# untitled.net
KiCad netlist of a schematic drawn in EAGLE
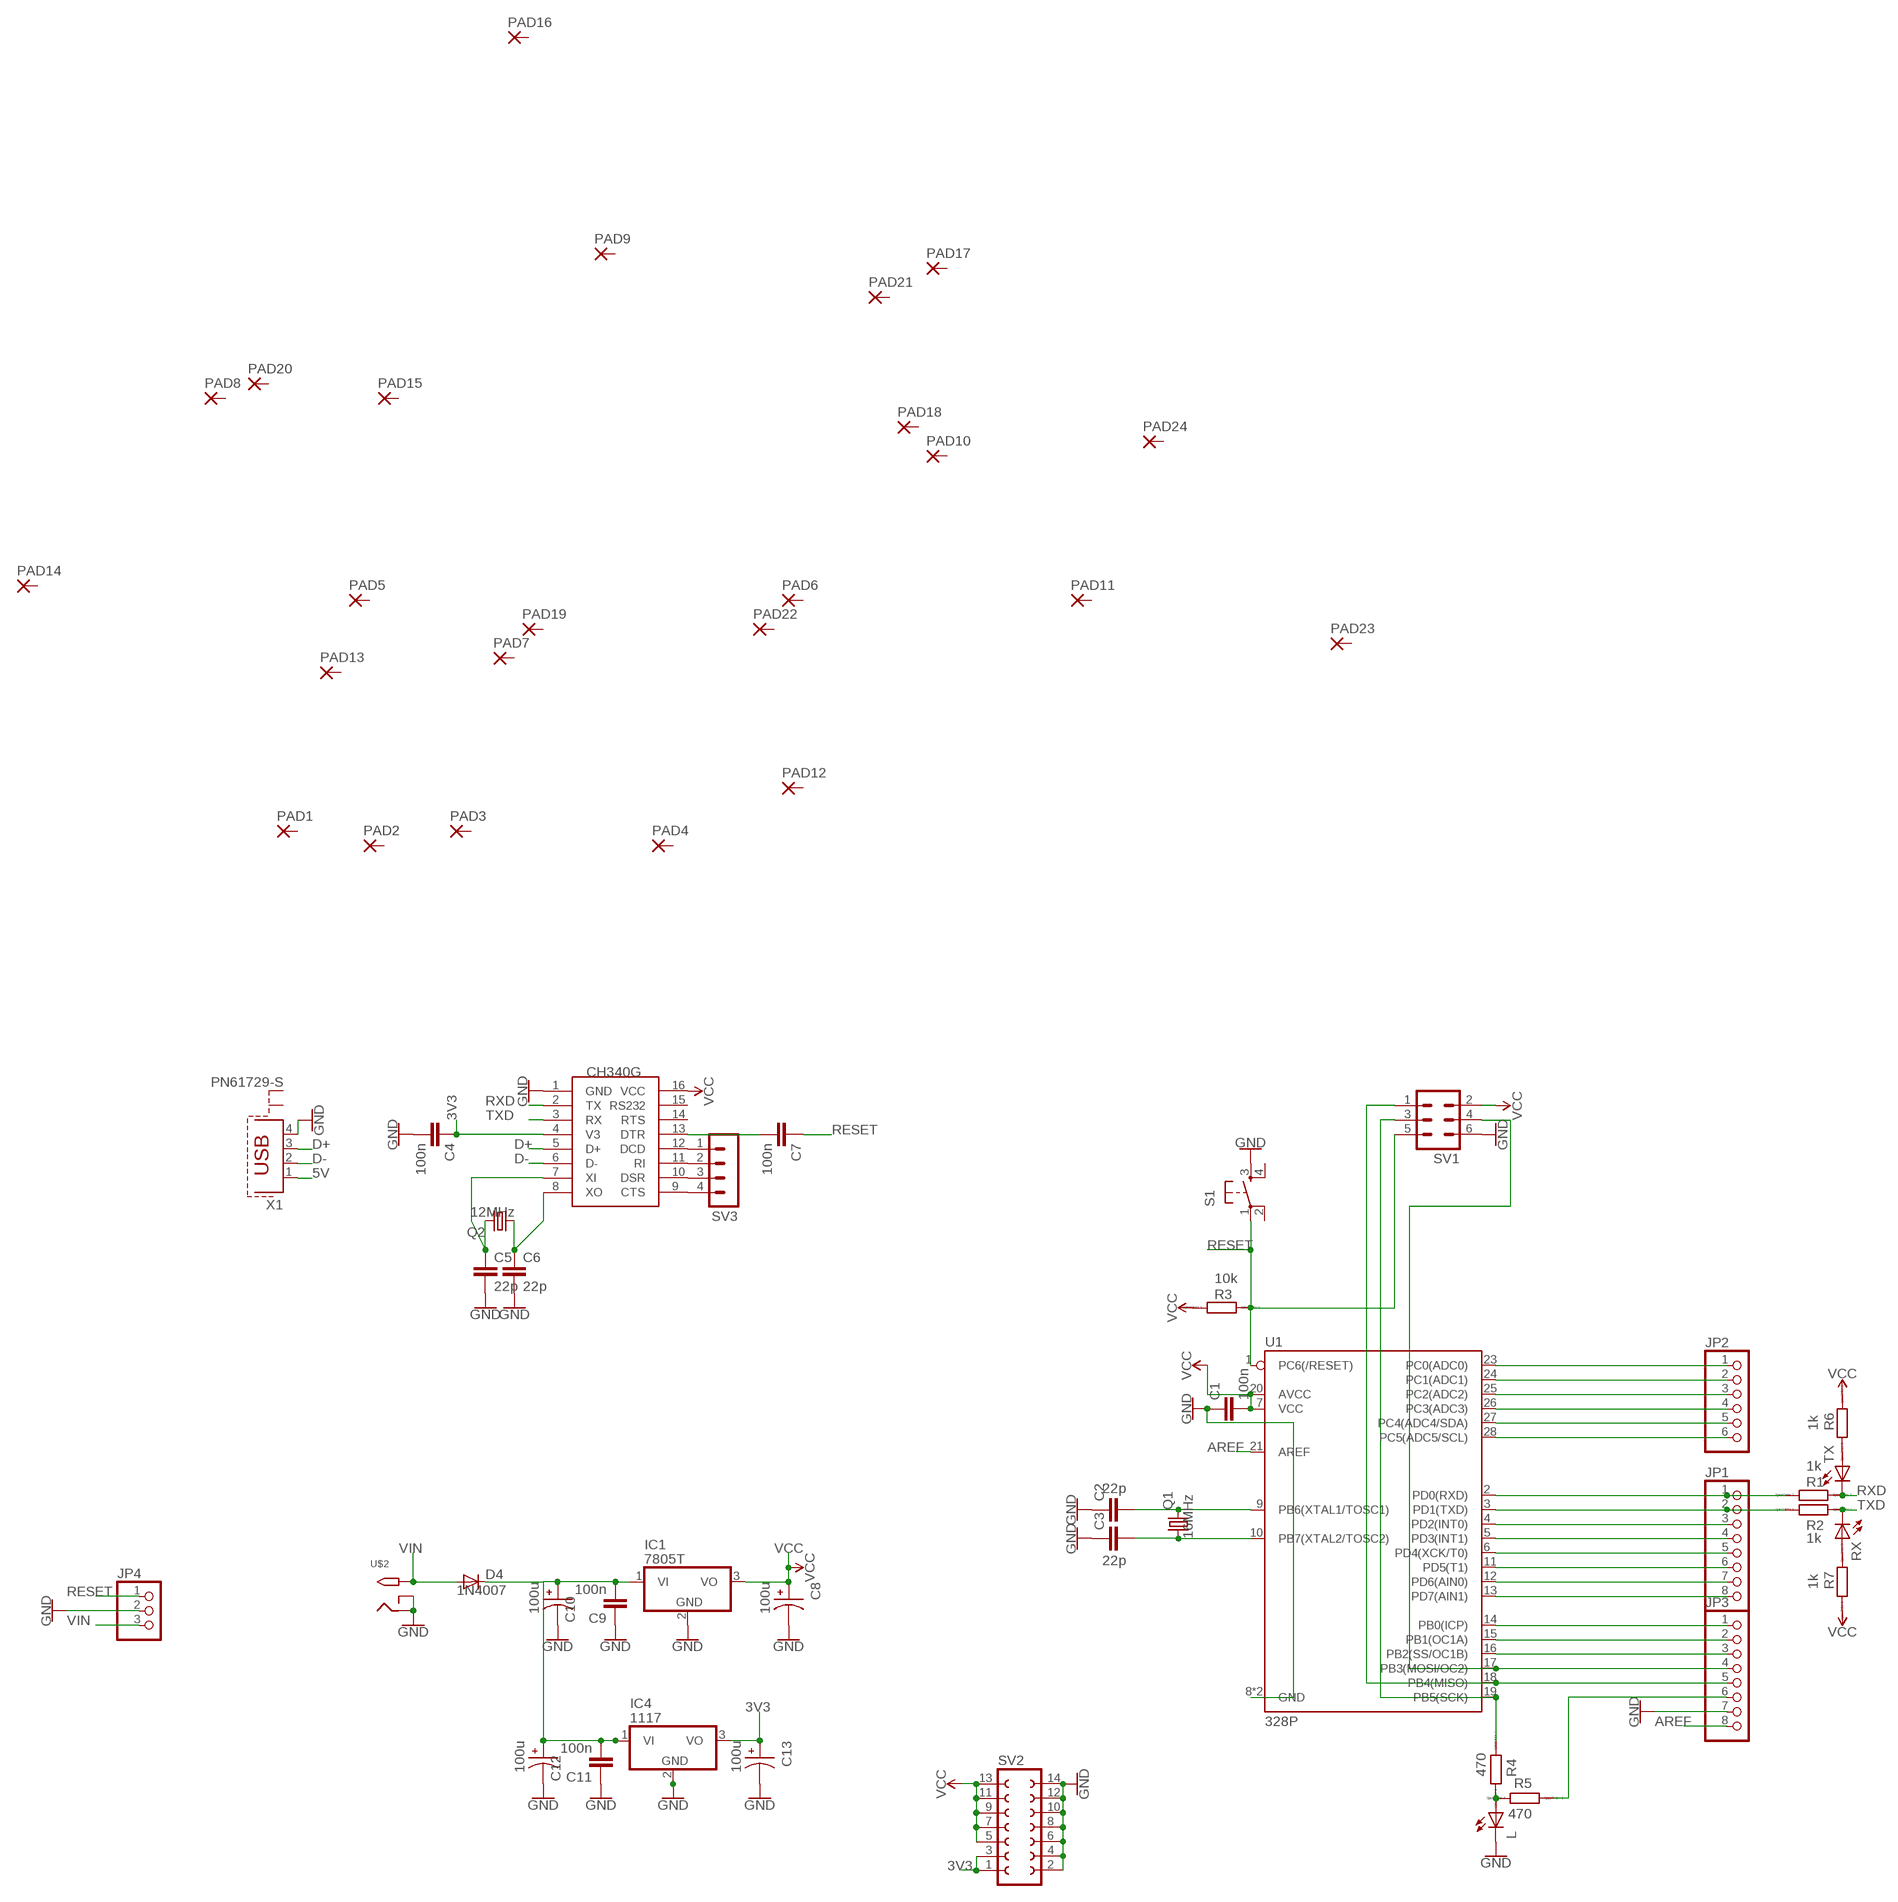
[diagram p0: schematic, sheet 1]

(export (version "E")
  (design (tool "Eeschema 10.0.6"))
  (components
    (comp (ref "C1")
      (value "100n")
      (footprint "eagle-import:C2.5-3")
      (libsource (lib "eagle-import") (part "C2,5-3"))
    )
    (comp (ref "C2")
      (value "22p")
      (footprint "eagle-import:C2.5-3")
      (libsource (lib "eagle-import") (part "C2,5-3"))
    )
    (comp (ref "C3")
      (value "22p")
      (footprint "eagle-import:C2.5-3")
      (libsource (lib "eagle-import") (part "C2,5-3"))
    )
    (comp (ref "C4")
      (value "100n")
      (footprint "eagle-import:C2.5-3")
      (libsource (lib "eagle-import") (part "C2,5-3"))
    )
    (comp (ref "C5")
      (value "22p")
      (footprint "eagle-import:C2.5-3")
      (libsource (lib "eagle-import") (part "C2,5-3"))
    )
    (comp (ref "C6")
      (value "22p")
      (footprint "eagle-import:C2.5-3")
      (libsource (lib "eagle-import") (part "C2,5-3"))
    )
    (comp (ref "C7")
      (value "100n")
      (footprint "eagle-import:C2.5-3")
      (libsource (lib "eagle-import") (part "C2,5-3"))
    )
    (comp (ref "C8")
      (value "100u")
      (footprint "eagle-import:CAPPRD500W50D500H1100")
      (fields (field (name "MF") "Panasonic") (field (name "MP") "ECA1VHG100B"))
      (libsource (lib "eagle-import") (part "ECA1VHG100B"))
    )
    (comp (ref "C9")
      (value "100n")
      (footprint "eagle-import:C2.5-3")
      (libsource (lib "eagle-import") (part "C2,5-3"))
    )
    (comp (ref "C10")
      (value "100u")
      (footprint "eagle-import:CAPPRD500W50D500H1100")
      (fields (field (name "MF") "Panasonic") (field (name "MP") "ECA1VHG100B"))
      (libsource (lib "eagle-import") (part "ECA1VHG100B"))
    )
    (comp (ref "C11")
      (value "100n")
      (footprint "eagle-import:C2.5-3")
      (libsource (lib "eagle-import") (part "C2,5-3"))
    )
    (comp (ref "C12")
      (value "100u")
      (footprint "eagle-import:CAPPRD500W50D500H1100")
      (fields (field (name "MF") "Panasonic") (field (name "MP") "ECA1VHG100B"))
      (libsource (lib "eagle-import") (part "ECA1VHG100B"))
    )
    (comp (ref "C13")
      (value "100u")
      (footprint "eagle-import:CAPPRD500W50D500H1100")
      (fields (field (name "MF") "Panasonic") (field (name "MP") "ECA1VHG100B"))
      (libsource (lib "eagle-import") (part "ECA1VHG100B"))
    )
    (comp (ref "D4")
      (value "1N4007")
      (footprint "eagle-import:DO41-10")
      (libsource (lib "eagle-import") (part "1N4004"))
    )
    (comp (ref "IC1")
      (value "7805T")
      (footprint "eagle-import:TO220H")
      (libsource (lib "eagle-import") (part "78T05"))
    )
    (comp (ref "IC4")
      (value "1117")
      (footprint "eagle-import:TO220H")
      (libsource (lib "eagle-import") (part "78T05"))
    )
    (comp (ref "JP1")
      (value "PINHD-1X8CLEANBIG")
      (footprint "eagle-import:1X08-CLEANBIG")
      (libsource (lib "eagle-import") (part "PINHD-1X8CLEANBIG"))
    )
    (comp (ref "JP2")
      (value "PINHD-1X6")
      (footprint "eagle-import:1X06")
      (libsource (lib "eagle-import") (part "PINHD-1X6"))
    )
    (comp (ref "JP3")
      (value "PINHD-1X8CLEANBIG")
      (footprint "eagle-import:1X08-CLEANBIG")
      (libsource (lib "eagle-import") (part "PINHD-1X8CLEANBIG"))
    )
    (comp (ref "JP4")
      (value "PINHD-1X3")
      (footprint "eagle-import:1X03")
      (libsource (lib "eagle-import") (part "PINHD-1X3"))
    )
    (comp (ref "L")
      (value "LED3MM")
      (footprint "eagle-import:LED3MM")
      (libsource (lib "eagle-import") (part "LED3MM"))
    )
    (comp (ref "PAD1")
      (value "SMD5")
      (footprint "eagle-import:SMD2,54-5,08")
      (libsource (lib "eagle-import") (part "SMD5"))
    )
    (comp (ref "PAD2")
      (value "SMD5")
      (footprint "eagle-import:SMD2,54-5,08")
      (libsource (lib "eagle-import") (part "SMD5"))
    )
    (comp (ref "PAD3")
      (value "SMD5")
      (footprint "eagle-import:SMD2,54-5,08")
      (libsource (lib "eagle-import") (part "SMD5"))
    )
    (comp (ref "PAD4")
      (value "SMD5")
      (footprint "eagle-import:SMD2,54-5,08")
      (libsource (lib "eagle-import") (part "SMD5"))
    )
    (comp (ref "PAD5")
      (value "SMD5")
      (footprint "eagle-import:SMD2,54-5,08")
      (libsource (lib "eagle-import") (part "SMD5"))
    )
    (comp (ref "PAD6")
      (value "SMD5")
      (footprint "eagle-import:SMD2,54-5,08")
      (libsource (lib "eagle-import") (part "SMD5"))
    )
    (comp (ref "PAD7")
      (value "SMD5")
      (footprint "eagle-import:SMD2,54-5,08")
      (libsource (lib "eagle-import") (part "SMD5"))
    )
    (comp (ref "PAD8")
      (value "SMD5")
      (footprint "eagle-import:SMD2,54-5,08")
      (libsource (lib "eagle-import") (part "SMD5"))
    )
    (comp (ref "PAD9")
      (value "SMD5")
      (footprint "eagle-import:SMD2,54-5,08")
      (libsource (lib "eagle-import") (part "SMD5"))
    )
    (comp (ref "PAD10")
      (value "SMD5")
      (footprint "eagle-import:SMD2,54-5,08")
      (libsource (lib "eagle-import") (part "SMD5"))
    )
    (comp (ref "PAD11")
      (value "SMD5")
      (footprint "eagle-import:SMD2,54-5,08")
      (libsource (lib "eagle-import") (part "SMD5"))
    )
    (comp (ref "PAD12")
      (value "SMD5")
      (footprint "eagle-import:SMD2,54-5,08")
      (libsource (lib "eagle-import") (part "SMD5"))
    )
    (comp (ref "PAD13")
      (value "SMD5")
      (footprint "eagle-import:SMD2,54-5,08")
      (libsource (lib "eagle-import") (part "SMD5"))
    )
    (comp (ref "PAD14")
      (value "SMD5")
      (footprint "eagle-import:SMD2,54-5,08")
      (libsource (lib "eagle-import") (part "SMD5"))
    )
    (comp (ref "PAD15")
      (value "SMD5")
      (footprint "eagle-import:SMD2,54-5,08")
      (libsource (lib "eagle-import") (part "SMD5"))
    )
    (comp (ref "PAD16")
      (value "SMD5")
      (footprint "eagle-import:SMD2,54-5,08")
      (libsource (lib "eagle-import") (part "SMD5"))
    )
    (comp (ref "PAD17")
      (value "SMD5")
      (footprint "eagle-import:SMD2,54-5,08")
      (libsource (lib "eagle-import") (part "SMD5"))
    )
    (comp (ref "PAD18")
      (value "SMD5")
      (footprint "eagle-import:SMD2,54-5,08")
      (libsource (lib "eagle-import") (part "SMD5"))
    )
    (comp (ref "PAD19")
      (value "SMD5")
      (footprint "eagle-import:SMD2,54-5,08")
      (libsource (lib "eagle-import") (part "SMD5"))
    )
    (comp (ref "PAD20")
      (value "SMD5")
      (footprint "eagle-import:SMD2,54-5,08")
      (libsource (lib "eagle-import") (part "SMD5"))
    )
    (comp (ref "PAD21")
      (value "SMD5")
      (footprint "eagle-import:SMD2,54-5,08")
      (libsource (lib "eagle-import") (part "SMD5"))
    )
    (comp (ref "PAD22")
      (value "SMD5")
      (footprint "eagle-import:SMD2,54-5,08")
      (libsource (lib "eagle-import") (part "SMD5"))
    )
    (comp (ref "PAD23")
      (value "SMD5")
      (footprint "eagle-import:SMD2,54-5,08")
      (libsource (lib "eagle-import") (part "SMD5"))
    )
    (comp (ref "PAD24")
      (value "SMD5")
      (footprint "eagle-import:SMD2,54-5,08")
      (libsource (lib "eagle-import") (part "SMD5"))
    )
    (comp (ref "Q1")
      (value "16MHz")
      (footprint "eagle-import:HC49_S")
      (libsource (lib "eagle-import") (part "CRYSTALHC49S"))
    )
    (comp (ref "Q2")
      (value "12MHz")
      (footprint "eagle-import:HC49_S")
      (libsource (lib "eagle-import") (part "CRYSTALHC49S"))
    )
    (comp (ref "R1")
      (value "1k")
      (footprint "eagle-import:0204_7")
      (libsource (lib "eagle-import") (part "R0204/7"))
    )
    (comp (ref "R2")
      (value "1k")
      (footprint "eagle-import:0204_7")
      (libsource (lib "eagle-import") (part "R0204/7"))
    )
    (comp (ref "R3")
      (value "10k")
      (footprint "eagle-import:0204_7")
      (libsource (lib "eagle-import") (part "R0204/7"))
    )
    (comp (ref "R4")
      (value "470")
      (footprint "eagle-import:0204_7")
      (libsource (lib "eagle-import") (part "R0204/7"))
    )
    (comp (ref "R5")
      (value "470")
      (footprint "eagle-import:0204_7")
      (libsource (lib "eagle-import") (part "R0204/7"))
    )
    (comp (ref "R6")
      (value "1k")
      (footprint "eagle-import:0204_7")
      (libsource (lib "eagle-import") (part "R0204/7"))
    )
    (comp (ref "R7")
      (value "1k")
      (footprint "eagle-import:0204_7")
      (libsource (lib "eagle-import") (part "R0204/7"))
    )
    (comp (ref "RX")
      (value "LED3MM")
      (footprint "eagle-import:LED3MM")
      (libsource (lib "eagle-import") (part "LED3MM"))
    )
    (comp (ref "S1")
      (value "TAC_SWITCHPTH")
      (footprint "eagle-import:TACTILE-PTH")
      (libsource (lib "eagle-import") (part "TAC_SWITCHPTH"))
    )
    (comp (ref "SV1")
      (value "MA03-2")
      (footprint "eagle-import:MA03-2")
      (libsource (lib "eagle-import") (part "MA03-2"))
    )
    (comp (ref "SV2")
      (value "FE07-2")
      (footprint "eagle-import:FE07-2")
      (libsource (lib "eagle-import") (part "FE07-2"))
    )
    (comp (ref "SV3")
      (value "MA04-1")
      (footprint "eagle-import:MA04-1")
      (libsource (lib "eagle-import") (part "MA04-1"))
    )
    (comp (ref "TX")
      (value "LED3MM")
      (footprint "eagle-import:LED3MM")
      (libsource (lib "eagle-import") (part "LED3MM"))
    )
    (comp (ref "U$1")
      (value "CH340G")
      (footprint "eagle-import:SOIC16")
      (libsource (lib "eagle-import") (part "CH340G"))
    )
    (comp (ref "U$2")
      (value "2.1MMJACKTHM")
      (footprint "eagle-import:PJ-102A")
      (libsource (lib "eagle-import") (part "2.1MMJACKTHM"))
    )
    (comp (ref "U1")
      (value "328P")
      (footprint "eagle-import:DIP28")
      (libsource (lib "eagle-import") (part "ATMEGA328P_PDIP"))
    )
    (comp (ref "X1")
      (value "PN61729-S")
      (footprint "eagle-import:PN61729-S")
      (libsource (lib "eagle-import") (part "PN61729-S"))
    )
  )
  (nets
    (net (code "1") (name "/3V3") (class "Default")
      (node (ref "C13") (pin "P") (pinfunction "P_P") (pintype "passive"))
      (node (ref "C4") (pin "1") (pinfunction "1_1") (pintype "passive"))
      (node (ref "IC4") (pin "3") (pinfunction "VO_3") (pintype "passive"))
      (node (ref "SV2") (pin "1") (pinfunction "1_1") (pintype "passive"))
      (node (ref "SV2") (pin "3") (pinfunction "3_3") (pintype "passive"))
      (node (ref "U$1") (pin "4") (pinfunction "V3_4") (pintype "bidirectional"))
    )
    (net (code "2") (name "/5V") (class "Default")
      (node (ref "X1") (pin "1") (pinfunction "1_1") (pintype "passive"))
    )
    (net (code "3") (name "/AREF") (class "Default")
      (node (ref "JP3") (pin "8") (pinfunction "8_8") (pintype "passive"))
      (node (ref "U1") (pin "21") (pinfunction "AREF_21") (pintype "bidirectional"))
    )
    (net (code "4") (name "/D+") (class "Default")
      (node (ref "U$1") (pin "5") (pinfunction "D+_5") (pintype "bidirectional"))
      (node (ref "X1") (pin "3") (pinfunction "3_3") (pintype "passive"))
    )
    (net (code "5") (name "/D-") (class "Default")
      (node (ref "U$1") (pin "6") (pinfunction "D-_6") (pintype "bidirectional"))
      (node (ref "X1") (pin "2") (pinfunction "2_2") (pintype "passive"))
    )
    (net (code "6") (name "/RESET") (class "Default")
      (node (ref "C7") (pin "1") (pinfunction "1_1") (pintype "passive"))
      (node (ref "JP4") (pin "1") (pinfunction "1_1") (pintype "passive"))
      (node (ref "R3") (pin "2") (pinfunction "2_2") (pintype "passive"))
      (node (ref "S1") (pin "1") (pinfunction "1_1") (pintype "passive"))
      (node (ref "SV1") (pin "5") (pinfunction "5_5") (pintype "passive"))
      (node (ref "U1") (pin "1") (pinfunction "PC6(/RESET)_1") (pintype "bidirectional"))
    )
    (net (code "7") (name "/RXD") (class "Default")
      (node (ref "R1") (pin "2") (pinfunction "2_2") (pintype "passive"))
      (node (ref "TX") (pin "K") (pinfunction "C_K") (pintype "passive"))
      (node (ref "U$1") (pin "2") (pinfunction "TX_2") (pintype "bidirectional"))
    )
    (net (code "8") (name "/TXD") (class "Default")
      (node (ref "R2") (pin "2") (pinfunction "2_2") (pintype "passive"))
      (node (ref "RX") (pin "K") (pinfunction "C_K") (pintype "passive"))
      (node (ref "U$1") (pin "3") (pinfunction "RX_3") (pintype "bidirectional"))
    )
    (net (code "9") (name "/VIN") (class "Default")
      (node (ref "D4") (pin "A") (pinfunction "A_A") (pintype "passive"))
      (node (ref "JP4") (pin "3") (pinfunction "3_3") (pintype "passive"))
      (node (ref "U$2") (pin "TIP") (pinfunction "TIP_TIP") (pintype "bidirectional"))
    )
    (net (code "10") (name "GND") (class "Default")
      (node (ref "C1") (pin "1") (pinfunction "1_1") (pintype "passive"))
      (node (ref "C10") (pin "N") (pinfunction "N_N") (pintype "passive"))
      (node (ref "C11") (pin "1") (pinfunction "1_1") (pintype "passive"))
      (node (ref "C12") (pin "N") (pinfunction "N_N") (pintype "passive"))
      (node (ref "C13") (pin "N") (pinfunction "N_N") (pintype "passive"))
      (node (ref "C2") (pin "1") (pinfunction "1_1") (pintype "passive"))
      (node (ref "C3") (pin "1") (pinfunction "1_1") (pintype "passive"))
      (node (ref "C4") (pin "2") (pinfunction "2_2") (pintype "passive"))
      (node (ref "C5") (pin "2") (pinfunction "2_2") (pintype "passive"))
      (node (ref "C6") (pin "2") (pinfunction "2_2") (pintype "passive"))
      (node (ref "C8") (pin "N") (pinfunction "N_N") (pintype "passive"))
      (node (ref "C9") (pin "1") (pinfunction "1_1") (pintype "passive"))
      (node (ref "IC1") (pin "2") (pinfunction "GND_2") (pintype "passive"))
      (node (ref "IC4") (pin "2") (pinfunction "GND_2") (pintype "passive"))
      (node (ref "JP3") (pin "7") (pinfunction "7_7") (pintype "passive"))
      (node (ref "JP4") (pin "2") (pinfunction "2_2") (pintype "passive"))
      (node (ref "L") (pin "K") (pinfunction "C_K") (pintype "passive"))
      (node (ref "S1") (pin "3") (pinfunction "3_3") (pintype "passive"))
      (node (ref "SV1") (pin "6") (pinfunction "6_6") (pintype "passive"))
      (node (ref "SV2") (pin "10") (pinfunction "10_10") (pintype "passive"))
      (node (ref "SV2") (pin "12") (pinfunction "12_12") (pintype "passive"))
      (node (ref "SV2") (pin "14") (pinfunction "14_14") (pintype "passive"))
      (node (ref "SV2") (pin "2") (pinfunction "2_2") (pintype "passive"))
      (node (ref "SV2") (pin "4") (pinfunction "4_4") (pintype "passive"))
      (node (ref "SV2") (pin "6") (pinfunction "6_6") (pintype "passive"))
      (node (ref "SV2") (pin "8") (pinfunction "8_8") (pintype "passive"))
      (node (ref "U$1") (pin "1") (pinfunction "GND_1") (pintype "bidirectional"))
      (node (ref "U$2") (pin "RING") (pinfunction "RING_RING") (pintype "bidirectional"))
      (node (ref "U$2") (pin "RING_SW") (pinfunction "RING_SW_RING_SW") (pintype "bidirectional"))
      (node (ref "U1") (pin "22") (pinfunction "GND_22") (pintype "bidirectional"))
      (node (ref "U1") (pin "8") (pinfunction "GND_8") (pintype "bidirectional"))
      (node (ref "X1") (pin "4") (pinfunction "4_4") (pintype "passive"))
    )
    (net (code "11") (name "Net-(IC1-VI)") (class "Default")
      (node (ref "C10") (pin "P") (pinfunction "P_P") (pintype "passive"))
      (node (ref "C11") (pin "2") (pinfunction "2_2") (pintype "passive"))
      (node (ref "C12") (pin "P") (pinfunction "P_P") (pintype "passive"))
      (node (ref "C9") (pin "2") (pinfunction "2_2") (pintype "passive"))
      (node (ref "D4") (pin "C") (pinfunction "C_C") (pintype "passive"))
      (node (ref "IC1") (pin "1") (pinfunction "VI_1") (pintype "input"))
      (node (ref "IC4") (pin "1") (pinfunction "VI_1") (pintype "input"))
    )
    (net (code "12") (name "Net-(JP3-Pad6)") (class "Default")
      (node (ref "JP3") (pin "6") (pinfunction "6_6") (pintype "passive"))
      (node (ref "R5") (pin "1") (pinfunction "1_1") (pintype "passive"))
    )
    (net (code "13") (name "Net-(L-PadA)") (class "Default")
      (node (ref "L") (pin "A") (pinfunction "A_A") (pintype "passive"))
      (node (ref "R4") (pin "1") (pinfunction "1_1") (pintype "passive"))
      (node (ref "R5") (pin "2") (pinfunction "2_2") (pintype "passive"))
    )
    (net (code "14") (name "Net-(R6-Pad1)") (class "Default")
      (node (ref "R6") (pin "1") (pinfunction "1_1") (pintype "passive"))
      (node (ref "TX") (pin "A") (pinfunction "A_A") (pintype "passive"))
    )
    (net (code "15") (name "Net-(R7-Pad2)") (class "Default")
      (node (ref "R7") (pin "2") (pinfunction "2_2") (pintype "passive"))
      (node (ref "RX") (pin "A") (pinfunction "A_A") (pintype "passive"))
    )
    (net (code "16") (name "Net-(U$1-CTS)") (class "Default")
      (node (ref "SV3") (pin "4") (pinfunction "4_4") (pintype "passive"))
      (node (ref "U$1") (pin "9") (pinfunction "CTS_9") (pintype "bidirectional"))
    )
    (net (code "17") (name "Net-(U$1-DCD)") (class "Default")
      (node (ref "SV3") (pin "1") (pinfunction "1_1") (pintype "passive"))
      (node (ref "U$1") (pin "12") (pinfunction "DCD_12") (pintype "bidirectional"))
    )
    (net (code "18") (name "Net-(U$1-DSR)") (class "Default")
      (node (ref "SV3") (pin "3") (pinfunction "3_3") (pintype "passive"))
      (node (ref "U$1") (pin "10") (pinfunction "DSR_10") (pintype "bidirectional"))
    )
    (net (code "19") (name "Net-(U$1-DTR)") (class "Default")
      (node (ref "C7") (pin "2") (pinfunction "2_2") (pintype "passive"))
      (node (ref "U$1") (pin "13") (pinfunction "DTR_13") (pintype "bidirectional"))
    )
    (net (code "20") (name "Net-(U$1-RI)") (class "Default")
      (node (ref "SV3") (pin "2") (pinfunction "2_2") (pintype "passive"))
      (node (ref "U$1") (pin "11") (pinfunction "RI_11") (pintype "bidirectional"))
    )
    (net (code "21") (name "Net-(U$1-XI)") (class "Default")
      (node (ref "C5") (pin "1") (pinfunction "1_1") (pintype "passive"))
      (node (ref "Q2") (pin "2") (pinfunction "2_2") (pintype "passive"))
      (node (ref "U$1") (pin "7") (pinfunction "XI_7") (pintype "bidirectional"))
    )
    (net (code "22") (name "Net-(U$1-XO)") (class "Default")
      (node (ref "C6") (pin "1") (pinfunction "1_1") (pintype "passive"))
      (node (ref "Q2") (pin "1") (pinfunction "1_1") (pintype "passive"))
      (node (ref "U$1") (pin "8") (pinfunction "XO_8") (pintype "bidirectional"))
    )
    (net (code "23") (name "Net-(U1-PB0(ICP))") (class "Default")
      (node (ref "JP3") (pin "1") (pinfunction "1_1") (pintype "passive"))
      (node (ref "U1") (pin "14") (pinfunction "PB0(ICP)_14") (pintype "bidirectional"))
    )
    (net (code "24") (name "Net-(U1-PB1(OC1A))") (class "Default")
      (node (ref "JP3") (pin "2") (pinfunction "2_2") (pintype "passive"))
      (node (ref "U1") (pin "15") (pinfunction "PB1(OC1A)_15") (pintype "bidirectional"))
    )
    (net (code "25") (name "Net-(U1-PB2(SS{slash}OC1B))") (class "Default")
      (node (ref "JP3") (pin "3") (pinfunction "3_3") (pintype "passive"))
      (node (ref "U1") (pin "16") (pinfunction "PB2(SS/OC1B)_16") (pintype "bidirectional"))
    )
    (net (code "26") (name "Net-(U1-PB3(MOSI{slash}OC2))") (class "Default")
      (node (ref "JP3") (pin "4") (pinfunction "4_4") (pintype "passive"))
      (node (ref "SV1") (pin "4") (pinfunction "4_4") (pintype "passive"))
      (node (ref "U1") (pin "17") (pinfunction "PB3(MOSI/OC2)_17") (pintype "bidirectional"))
    )
    (net (code "27") (name "Net-(U1-PB4(MISO))") (class "Default")
      (node (ref "JP3") (pin "5") (pinfunction "5_5") (pintype "passive"))
      (node (ref "SV1") (pin "1") (pinfunction "1_1") (pintype "passive"))
      (node (ref "U1") (pin "18") (pinfunction "PB4(MISO)_18") (pintype "bidirectional"))
    )
    (net (code "28") (name "Net-(U1-PB5(SCK))") (class "Default")
      (node (ref "R4") (pin "2") (pinfunction "2_2") (pintype "passive"))
      (node (ref "SV1") (pin "3") (pinfunction "3_3") (pintype "passive"))
      (node (ref "U1") (pin "19") (pinfunction "PB5(SCK)_19") (pintype "bidirectional"))
    )
    (net (code "29") (name "Net-(U1-PB6(XTAL1{slash}TOSC1))") (class "Default")
      (node (ref "C2") (pin "2") (pinfunction "2_2") (pintype "passive"))
      (node (ref "Q1") (pin "2") (pinfunction "2_2") (pintype "passive"))
      (node (ref "U1") (pin "9") (pinfunction "PB6(XTAL1/TOSC1)_9") (pintype "bidirectional"))
    )
    (net (code "30") (name "Net-(U1-PB7(XTAL2{slash}TOSC2))") (class "Default")
      (node (ref "C3") (pin "2") (pinfunction "2_2") (pintype "passive"))
      (node (ref "Q1") (pin "1") (pinfunction "1_1") (pintype "passive"))
      (node (ref "U1") (pin "10") (pinfunction "PB7(XTAL2/TOSC2)_10") (pintype "bidirectional"))
    )
    (net (code "31") (name "Net-(U1-PC0(ADC0))") (class "Default")
      (node (ref "JP2") (pin "1") (pinfunction "1_1") (pintype "passive"))
      (node (ref "U1") (pin "23") (pinfunction "PC0(ADC0)_23") (pintype "bidirectional"))
    )
    (net (code "32") (name "Net-(U1-PC1(ADC1))") (class "Default")
      (node (ref "JP2") (pin "2") (pinfunction "2_2") (pintype "passive"))
      (node (ref "U1") (pin "24") (pinfunction "PC1(ADC1)_24") (pintype "bidirectional"))
    )
    (net (code "33") (name "Net-(U1-PC2(ADC2))") (class "Default")
      (node (ref "JP2") (pin "3") (pinfunction "3_3") (pintype "passive"))
      (node (ref "U1") (pin "25") (pinfunction "PC2(ADC2)_25") (pintype "bidirectional"))
    )
    (net (code "34") (name "Net-(U1-PC3(ADC3))") (class "Default")
      (node (ref "JP2") (pin "4") (pinfunction "4_4") (pintype "passive"))
      (node (ref "U1") (pin "26") (pinfunction "PC3(ADC3)_26") (pintype "bidirectional"))
    )
    (net (code "35") (name "Net-(U1-PC4(ADC4{slash}SDA))") (class "Default")
      (node (ref "JP2") (pin "5") (pinfunction "5_5") (pintype "passive"))
      (node (ref "U1") (pin "27") (pinfunction "PC4(ADC4/SDA)_27") (pintype "bidirectional"))
    )
    (net (code "36") (name "Net-(U1-PC5(ADC5{slash}SCL))") (class "Default")
      (node (ref "JP2") (pin "6") (pinfunction "6_6") (pintype "passive"))
      (node (ref "U1") (pin "28") (pinfunction "PC5(ADC5/SCL)_28") (pintype "bidirectional"))
    )
    (net (code "37") (name "Net-(U1-PD0(RXD))") (class "Default")
      (node (ref "JP1") (pin "1") (pinfunction "1_1") (pintype "passive"))
      (node (ref "R1") (pin "1") (pinfunction "1_1") (pintype "passive"))
      (node (ref "U1") (pin "2") (pinfunction "PD0(RXD)_2") (pintype "bidirectional"))
    )
    (net (code "38") (name "Net-(U1-PD1(TXD))") (class "Default")
      (node (ref "JP1") (pin "2") (pinfunction "2_2") (pintype "passive"))
      (node (ref "R2") (pin "1") (pinfunction "1_1") (pintype "passive"))
      (node (ref "U1") (pin "3") (pinfunction "PD1(TXD)_3") (pintype "bidirectional"))
    )
    (net (code "39") (name "Net-(U1-PD2(INT0))") (class "Default")
      (node (ref "JP1") (pin "3") (pinfunction "3_3") (pintype "passive"))
      (node (ref "U1") (pin "4") (pinfunction "PD2(INT0)_4") (pintype "bidirectional"))
    )
    (net (code "40") (name "Net-(U1-PD3(INT1))") (class "Default")
      (node (ref "JP1") (pin "4") (pinfunction "4_4") (pintype "passive"))
      (node (ref "U1") (pin "5") (pinfunction "PD3(INT1)_5") (pintype "bidirectional"))
    )
    (net (code "41") (name "Net-(U1-PD4(XCK{slash}T0))") (class "Default")
      (node (ref "JP1") (pin "5") (pinfunction "5_5") (pintype "passive"))
      (node (ref "U1") (pin "6") (pinfunction "PD4(XCK/T0)_6") (pintype "bidirectional"))
    )
    (net (code "42") (name "Net-(U1-PD5(T1))") (class "Default")
      (node (ref "JP1") (pin "6") (pinfunction "6_6") (pintype "passive"))
      (node (ref "U1") (pin "11") (pinfunction "PD5(T1)_11") (pintype "bidirectional"))
    )
    (net (code "43") (name "Net-(U1-PD6(AIN0))") (class "Default")
      (node (ref "JP1") (pin "7") (pinfunction "7_7") (pintype "passive"))
      (node (ref "U1") (pin "12") (pinfunction "PD6(AIN0)_12") (pintype "bidirectional"))
    )
    (net (code "44") (name "Net-(U1-PD7(AIN1))") (class "Default")
      (node (ref "JP1") (pin "8") (pinfunction "8_8") (pintype "passive"))
      (node (ref "U1") (pin "13") (pinfunction "PD7(AIN1)_13") (pintype "bidirectional"))
    )
    (net (code "45") (name "VCC") (class "Default")
      (node (ref "C1") (pin "2") (pinfunction "2_2") (pintype "passive"))
      (node (ref "C8") (pin "P") (pinfunction "P_P") (pintype "passive"))
      (node (ref "IC1") (pin "3") (pinfunction "VO_3") (pintype "passive"))
      (node (ref "R3") (pin "1") (pinfunction "1_1") (pintype "passive"))
      (node (ref "R6") (pin "2") (pinfunction "2_2") (pintype "passive"))
      (node (ref "R7") (pin "1") (pinfunction "1_1") (pintype "passive"))
      (node (ref "SV1") (pin "2") (pinfunction "2_2") (pintype "passive"))
      (node (ref "SV2") (pin "11") (pinfunction "11_11") (pintype "passive"))
      (node (ref "SV2") (pin "13") (pinfunction "13_13") (pintype "passive"))
      (node (ref "SV2") (pin "5") (pinfunction "5_5") (pintype "passive"))
      (node (ref "SV2") (pin "7") (pinfunction "7_7") (pintype "passive"))
      (node (ref "SV2") (pin "9") (pinfunction "9_9") (pintype "passive"))
      (node (ref "U$1") (pin "16") (pinfunction "VCC_16") (pintype "bidirectional"))
      (node (ref "U1") (pin "20") (pinfunction "AVCC_20") (pintype "bidirectional"))
      (node (ref "U1") (pin "7") (pinfunction "VCC_7") (pintype "bidirectional"))
    )
    (net (code "46") (name "unconnected-(PAD1-P-Pad1)") (class "Default")
      (node (ref "PAD1") (pin "1") (pinfunction "P_1") (pintype "passive"))
    )
    (net (code "47") (name "unconnected-(PAD2-P-Pad1)") (class "Default")
      (node (ref "PAD2") (pin "1") (pinfunction "P_1") (pintype "passive"))
    )
    (net (code "48") (name "unconnected-(PAD3-P-Pad1)") (class "Default")
      (node (ref "PAD3") (pin "1") (pinfunction "P_1") (pintype "passive"))
    )
    (net (code "49") (name "unconnected-(PAD4-P-Pad1)") (class "Default")
      (node (ref "PAD4") (pin "1") (pinfunction "P_1") (pintype "passive"))
    )
    (net (code "50") (name "unconnected-(PAD5-P-Pad1)") (class "Default")
      (node (ref "PAD5") (pin "1") (pinfunction "P_1") (pintype "passive"))
    )
    (net (code "51") (name "unconnected-(PAD6-P-Pad1)") (class "Default")
      (node (ref "PAD6") (pin "1") (pinfunction "P_1") (pintype "passive"))
    )
    (net (code "52") (name "unconnected-(PAD7-P-Pad1)") (class "Default")
      (node (ref "PAD7") (pin "1") (pinfunction "P_1") (pintype "passive"))
    )
    (net (code "53") (name "unconnected-(PAD8-P-Pad1)") (class "Default")
      (node (ref "PAD8") (pin "1") (pinfunction "P_1") (pintype "passive"))
    )
    (net (code "54") (name "unconnected-(PAD9-P-Pad1)") (class "Default")
      (node (ref "PAD9") (pin "1") (pinfunction "P_1") (pintype "passive"))
    )
    (net (code "55") (name "unconnected-(PAD10-P-Pad1)") (class "Default")
      (node (ref "PAD10") (pin "1") (pinfunction "P_1") (pintype "passive"))
    )
    (net (code "56") (name "unconnected-(PAD11-P-Pad1)") (class "Default")
      (node (ref "PAD11") (pin "1") (pinfunction "P_1") (pintype "passive"))
    )
    (net (code "57") (name "unconnected-(PAD12-P-Pad1)") (class "Default")
      (node (ref "PAD12") (pin "1") (pinfunction "P_1") (pintype "passive"))
    )
    (net (code "58") (name "unconnected-(PAD13-P-Pad1)") (class "Default")
      (node (ref "PAD13") (pin "1") (pinfunction "P_1") (pintype "passive"))
    )
    (net (code "59") (name "unconnected-(PAD14-P-Pad1)") (class "Default")
      (node (ref "PAD14") (pin "1") (pinfunction "P_1") (pintype "passive"))
    )
    (net (code "60") (name "unconnected-(PAD15-P-Pad1)") (class "Default")
      (node (ref "PAD15") (pin "1") (pinfunction "P_1") (pintype "passive"))
    )
    (net (code "61") (name "unconnected-(PAD16-P-Pad1)") (class "Default")
      (node (ref "PAD16") (pin "1") (pinfunction "P_1") (pintype "passive"))
    )
    (net (code "62") (name "unconnected-(PAD17-P-Pad1)") (class "Default")
      (node (ref "PAD17") (pin "1") (pinfunction "P_1") (pintype "passive"))
    )
    (net (code "63") (name "unconnected-(PAD18-P-Pad1)") (class "Default")
      (node (ref "PAD18") (pin "1") (pinfunction "P_1") (pintype "passive"))
    )
    (net (code "64") (name "unconnected-(PAD19-P-Pad1)") (class "Default")
      (node (ref "PAD19") (pin "1") (pinfunction "P_1") (pintype "passive"))
    )
    (net (code "65") (name "unconnected-(PAD20-P-Pad1)") (class "Default")
      (node (ref "PAD20") (pin "1") (pinfunction "P_1") (pintype "passive"))
    )
    (net (code "66") (name "unconnected-(PAD21-P-Pad1)") (class "Default")
      (node (ref "PAD21") (pin "1") (pinfunction "P_1") (pintype "passive"))
    )
    (net (code "67") (name "unconnected-(PAD22-P-Pad1)") (class "Default")
      (node (ref "PAD22") (pin "1") (pinfunction "P_1") (pintype "passive"))
    )
    (net (code "68") (name "unconnected-(PAD23-P-Pad1)") (class "Default")
      (node (ref "PAD23") (pin "1") (pinfunction "P_1") (pintype "passive"))
    )
    (net (code "69") (name "unconnected-(PAD24-P-Pad1)") (class "Default")
      (node (ref "PAD24") (pin "1") (pinfunction "P_1") (pintype "passive"))
    )
    (net (code "70") (name "unconnected-(S1-Pad2)") (class "Default")
      (node (ref "S1") (pin "2") (pinfunction "2_2") (pintype "passive"))
    )
    (net (code "71") (name "unconnected-(S1-Pad4)") (class "Default")
      (node (ref "S1") (pin "4") (pinfunction "4_4") (pintype "passive"))
    )
    (net (code "72") (name "unconnected-(U$1-RS232-Pad15)") (class "Default")
      (node (ref "U$1") (pin "15") (pinfunction "RS232_15") (pintype "bidirectional"))
    )
    (net (code "73") (name "unconnected-(U$1-RTS-Pad14)") (class "Default")
      (node (ref "U$1") (pin "14") (pinfunction "RTS_14") (pintype "bidirectional"))
    )
    (net (code "74") (name "unconnected-(X1-PadS1)") (class "Default")
      (node (ref "X1") (pin "S1") (pinfunction "S1_S1") (pintype "passive"))
    )
    (net (code "75") (name "unconnected-(X1-PadS2)") (class "Default")
      (node (ref "X1") (pin "S2") (pinfunction "S2_S2") (pintype "passive"))
    )
  )
)
